# bitTree-Schem_2024-10-30.net
KiCad netlist of a schematic drawn in EasyEDA Pro
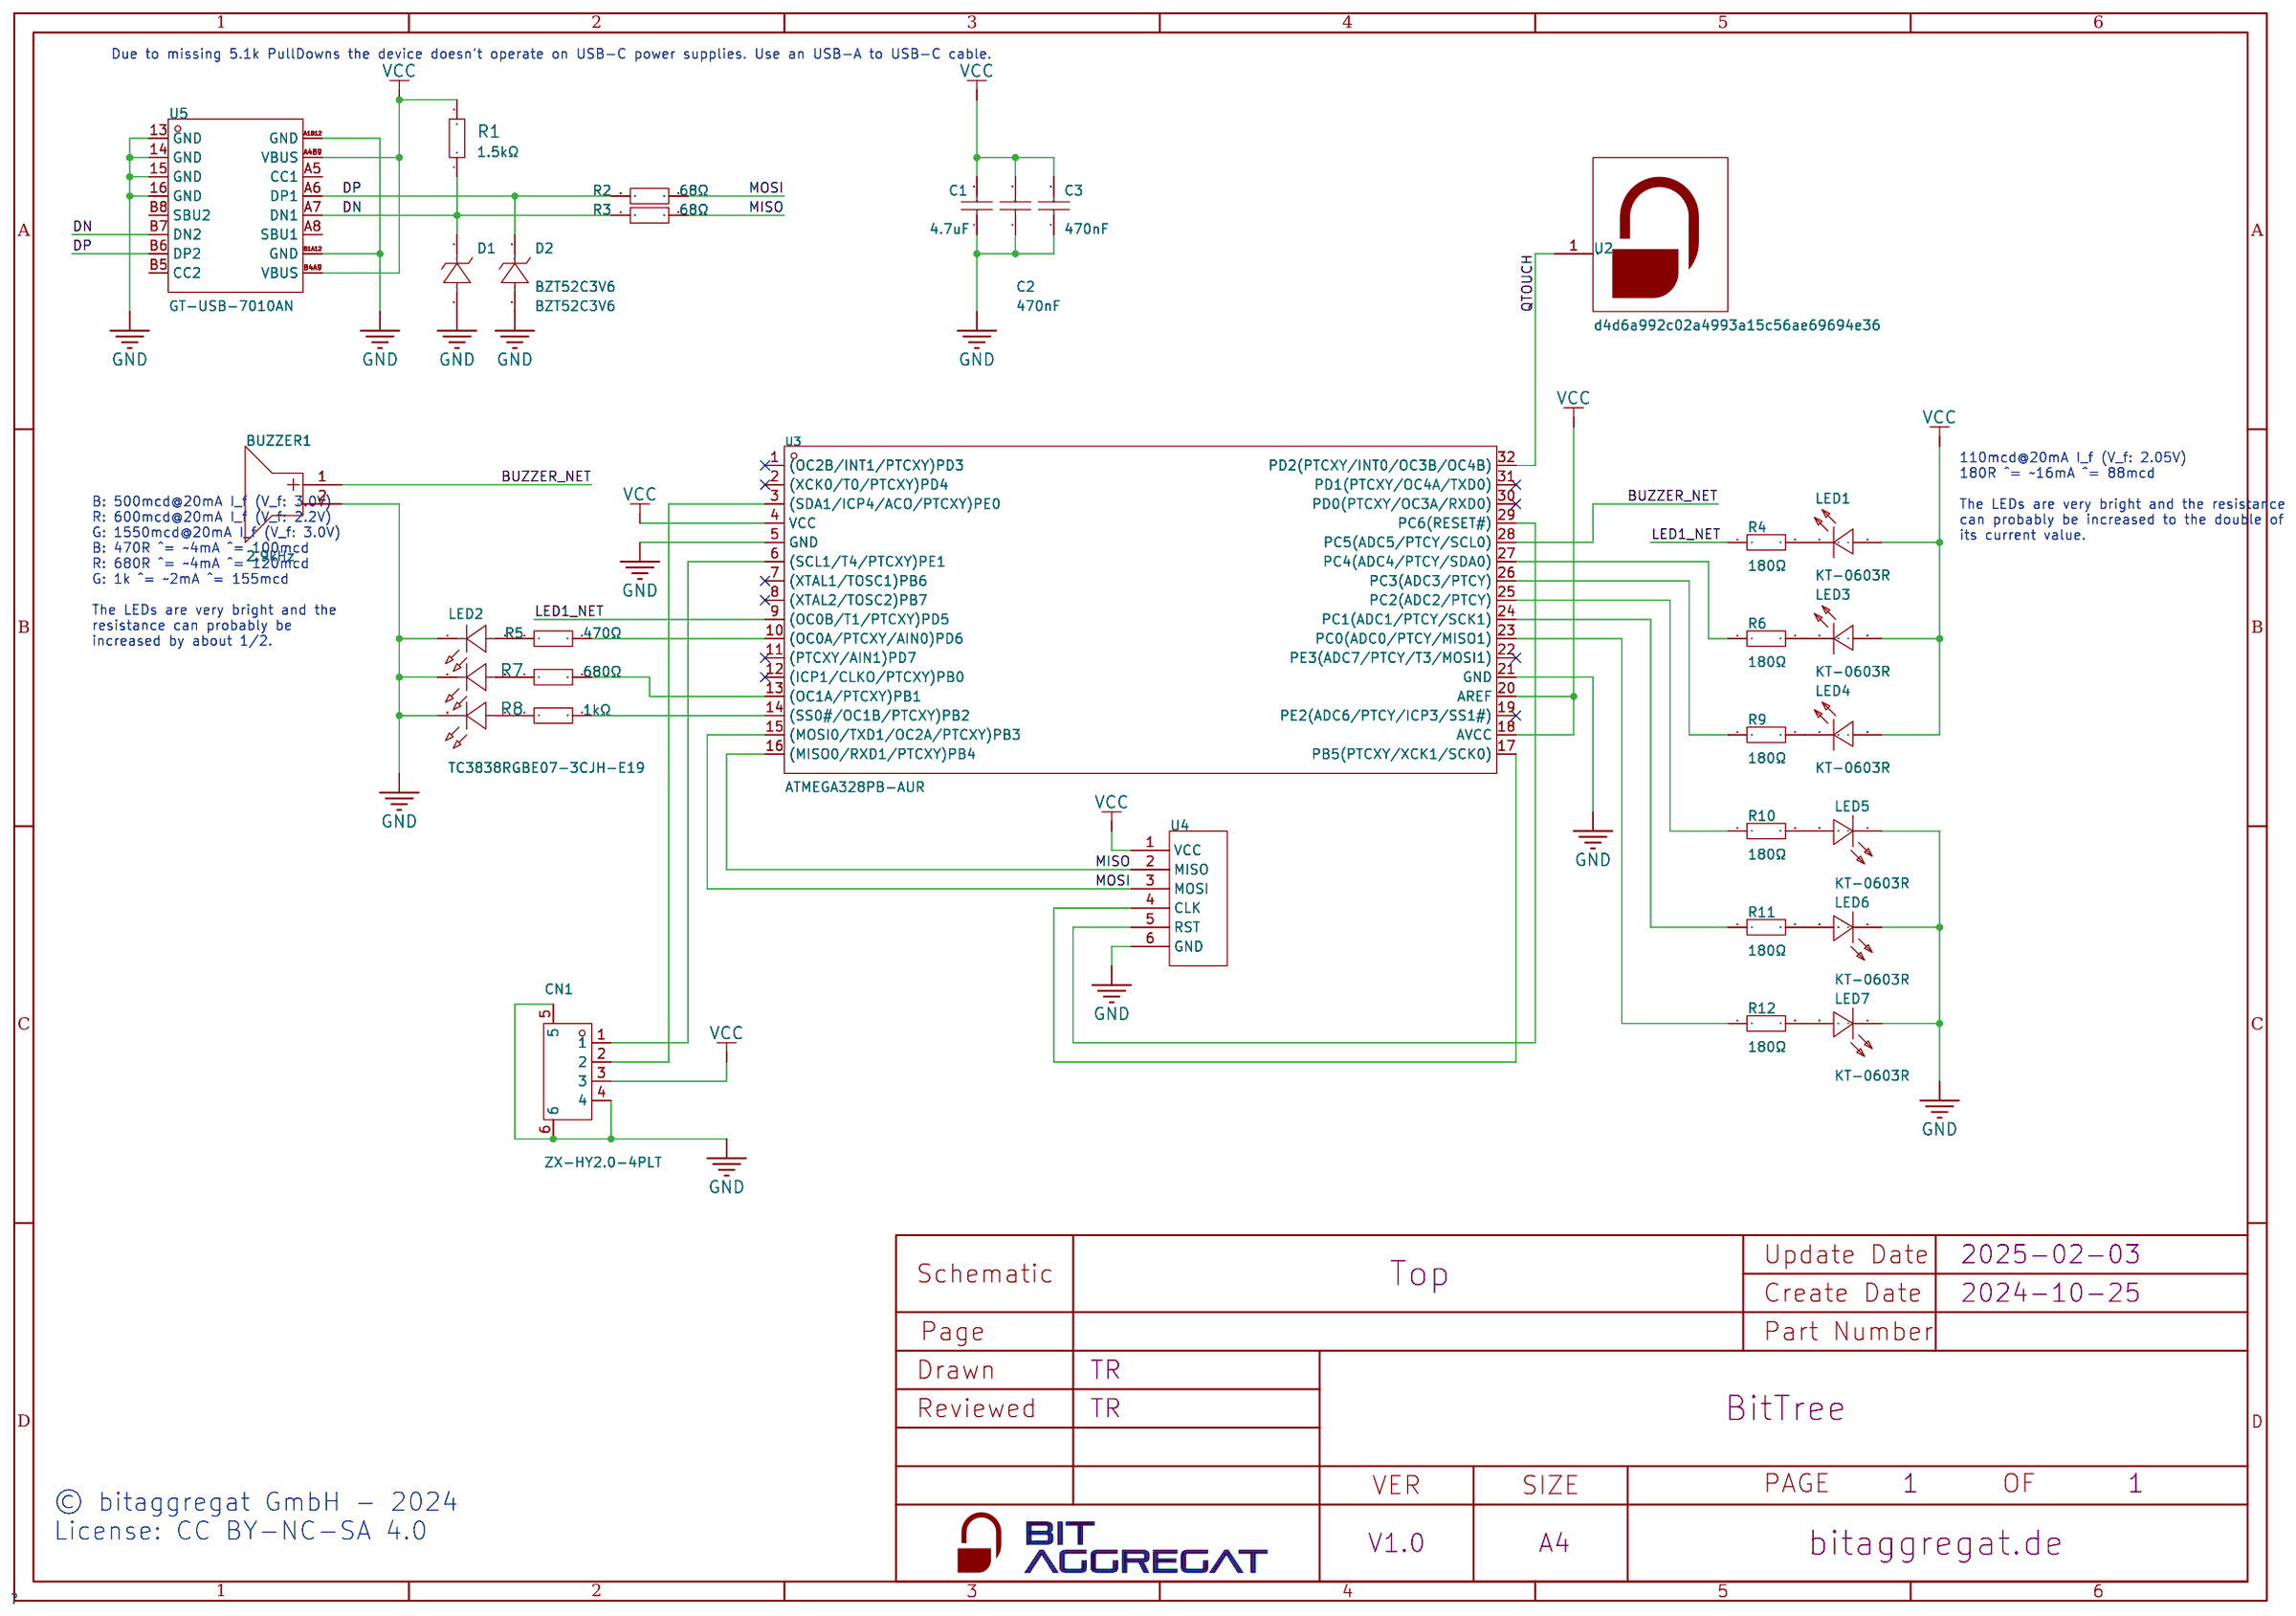
[diagram p0: schematic sheet]

(export (version "E")
  (design (tool "Eeschema 10.0.6"))
  (components
    (comp (ref "BUZZER1")
      (value "2.9kHz")
      (footprint "easyedapro:BUZ-TH_BD9.0-P5.00-D0.6-L-FD")
      (fields (field (name "Manufacturer Part") "Cy-9055-5029") (field (name "Manufacturer") "CY(超音)"))
      (libsource (lib "easyedapro") (part "CY-9055-5029"))
    )
    (comp (ref "C1")
      (value "4.7uF")
      (footprint "easyedapro:C0603")
      (fields
        (field (name "Manufacturer Part") "CL10A475KO8NNNC")
        (field (name "Manufacturer") "SAMSUNG(三星)")
      )
      (libsource (lib "easyedapro") (part "CL10A475KO8NNNC"))
    )
    (comp (ref "C2")
      (value "470nF")
      (footprint "easyedapro:C0603")
      (fields
        (field (name "Manufacturer Part") "CL10B474KA8NNNC")
        (field (name "Manufacturer") "SAMSUNG(三星)")
      )
      (libsource (lib "easyedapro") (part "CL10B474KA8NNNC"))
    )
    (comp (ref "C3")
      (value "470nF")
      (footprint "easyedapro:C0603")
      (fields
        (field (name "Manufacturer Part") "CL10B474KA8NNNC")
        (field (name "Manufacturer") "SAMSUNG(三星)")
      )
      (libsource (lib "easyedapro") (part "CL10B474KA8NNNC"))
    )
    (comp (ref "CN1")
      (value "ZX-HY2.0-4PLT")
      (footprint "easyedapro:CONN-SMD_4P-P2.00_HY2.0-4P")
      (fields (field (name "Manufacturer") "Megastar(兆星)"))
      (libsource (lib "easyedapro") (part "ZX-HY2.0-4PLT"))
    )
    (comp (ref "D1")
      (value "BZT52C3V6")
      (footprint "easyedapro:SOD-123_L2.7-W1.6-LS3.7-RD")
      (fields (field (name "Manufacturer") "宏迦橙"))
      (libsource (lib "easyedapro") (part "BZT52C3V6_C19077397"))
    )
    (comp (ref "D2")
      (value "BZT52C3V6")
      (footprint "easyedapro:SOD-123_L2.7-W1.6-LS3.7-RD")
      (fields (field (name "Manufacturer") "宏迦橙"))
      (libsource (lib "easyedapro") (part "BZT52C3V6_C19077397"))
    )
    (comp (ref "LED1")
      (value "KT-0603R")
      (footprint "easyedapro:LED0603-RD")
      (fields (field (name "Manufacturer") "KENTO"))
      (libsource (lib "easyedapro") (part "KT-0603R"))
    )
    (comp (ref "LED2")
      (value "TC3838RGBE07-3CJH-E19")
      (footprint "easyedapro:LED-SMD_6P-L3.5-W3.5-BL")
      (fields (field (name "Manufacturer") "TCWIN(天成)"))
      (libsource (lib "easyedapro") (part "TC3838RGBE07-3CJH-E19"))
    )
    (comp (ref "LED3")
      (value "KT-0603R")
      (footprint "easyedapro:LED0603-RD")
      (fields (field (name "Manufacturer") "KENTO"))
      (libsource (lib "easyedapro") (part "KT-0603R"))
    )
    (comp (ref "LED4")
      (value "KT-0603R")
      (footprint "easyedapro:LED0603-RD")
      (fields (field (name "Manufacturer") "KENTO"))
      (libsource (lib "easyedapro") (part "KT-0603R"))
    )
    (comp (ref "LED5")
      (value "KT-0603R")
      (footprint "easyedapro:LED0603-RD")
      (fields (field (name "Manufacturer") "KENTO"))
      (libsource (lib "easyedapro") (part "KT-0603R"))
    )
    (comp (ref "LED6")
      (value "KT-0603R")
      (footprint "easyedapro:LED0603-RD")
      (fields (field (name "Manufacturer") "KENTO"))
      (libsource (lib "easyedapro") (part "KT-0603R"))
    )
    (comp (ref "LED7")
      (value "KT-0603R")
      (footprint "easyedapro:LED0603-RD")
      (fields (field (name "Manufacturer") "KENTO"))
      (libsource (lib "easyedapro") (part "KT-0603R"))
    )
    (comp (ref "R1")
      (value "1.5kΩ")
      (footprint "easyedapro:R0603")
      (fields
        (field (name "Manufacturer Part") "0603WAF1501T5E")
        (field (name "Manufacturer") "UNI-ROYAL(厚声)")
      )
      (libsource (lib "easyedapro") (part "0603WAF1501T5E"))
    )
    (comp (ref "R2")
      (value "68Ω")
      (footprint "easyedapro:R0603")
      (fields
        (field (name "Manufacturer Part") "0603WAF680JT5E")
        (field (name "Manufacturer") "UNI-ROYAL(厚声)")
      )
      (libsource (lib "easyedapro") (part "0603WAF680JT5E"))
    )
    (comp (ref "R3")
      (value "68Ω")
      (footprint "easyedapro:R0603")
      (fields
        (field (name "Manufacturer Part") "0603WAF680JT5E")
        (field (name "Manufacturer") "UNI-ROYAL(厚声)")
      )
      (libsource (lib "easyedapro") (part "0603WAF680JT5E"))
    )
    (comp (ref "R4")
      (value "180Ω")
      (footprint "easyedapro:R0603")
      (fields
        (field (name "Manufacturer Part") "0603WAF1800T5E")
        (field (name "Manufacturer") "UNI-ROYAL(厚声)")
      )
      (libsource (lib "easyedapro") (part "0603WAF1800T5E"))
    )
    (comp (ref "R5")
      (value "470Ω")
      (footprint "easyedapro:R0603")
      (fields
        (field (name "Manufacturer Part") "0603WAF4700T5E")
        (field (name "Manufacturer") "UNI-ROYAL(厚声)")
      )
      (libsource (lib "easyedapro") (part "0603WAF4700T5E"))
    )
    (comp (ref "R6")
      (value "180Ω")
      (footprint "easyedapro:R0603")
      (fields
        (field (name "Manufacturer Part") "0603WAF1800T5E")
        (field (name "Manufacturer") "UNI-ROYAL(厚声)")
      )
      (libsource (lib "easyedapro") (part "0603WAF1800T5E"))
    )
    (comp (ref "R7")
      (value "680Ω")
      (footprint "easyedapro:R0603")
      (fields
        (field (name "Manufacturer Part") "0603WAF6800T5E")
        (field (name "Manufacturer") "UNI-ROYAL(厚声)")
      )
      (libsource (lib "easyedapro") (part "0603WAF6800T5E"))
    )
    (comp (ref "R8")
      (value "1kΩ")
      (footprint "easyedapro:R0603")
      (fields
        (field (name "Manufacturer Part") "0603WAF1001T5E")
        (field (name "Manufacturer") "UNI-ROYAL(厚声)")
      )
      (libsource (lib "easyedapro") (part "0603WAF1001T5E"))
    )
    (comp (ref "R9")
      (value "180Ω")
      (footprint "easyedapro:R0603")
      (fields
        (field (name "Manufacturer Part") "0603WAF1800T5E")
        (field (name "Manufacturer") "UNI-ROYAL(厚声)")
      )
      (libsource (lib "easyedapro") (part "0603WAF1800T5E"))
    )
    (comp (ref "R10")
      (value "180Ω")
      (footprint "easyedapro:R0603")
      (fields
        (field (name "Manufacturer Part") "0603WAF1800T5E")
        (field (name "Manufacturer") "UNI-ROYAL(厚声)")
      )
      (libsource (lib "easyedapro") (part "0603WAF1800T5E"))
    )
    (comp (ref "R11")
      (value "180Ω")
      (footprint "easyedapro:R0603")
      (fields
        (field (name "Manufacturer Part") "0603WAF1800T5E")
        (field (name "Manufacturer") "UNI-ROYAL(厚声)")
      )
      (libsource (lib "easyedapro") (part "0603WAF1800T5E"))
    )
    (comp (ref "R12")
      (value "180Ω")
      (footprint "easyedapro:R0603")
      (fields
        (field (name "Manufacturer Part") "0603WAF1800T5E")
        (field (name "Manufacturer") "UNI-ROYAL(厚声)")
      )
      (libsource (lib "easyedapro") (part "0603WAF1800T5E"))
    )
    (comp (ref "U2")
      (value "d4d6a992c02a4993a15c56ae69694e36")
      (footprint "easyedapro:QTouch-BA")
      (libsource (lib "easyedapro") (part "QTouch-BA"))
    )
    (comp (ref "U3")
      (value "ATMEGA328PB-AUR")
      (footprint "easyedapro:TQFP-32_L7.0-W7.0-P0.80-LS9.0-BL")
      (fields (field (name "Manufacturer") "MICROCHIP(美国微芯)"))
      (libsource (lib "easyedapro") (part "ATMEGA328PB-AUR"))
    )
    (comp (ref "U4")
      (value "~")
      (footprint "easyedapro:ProgrammingHeader")
      (libsource (lib "easyedapro") (part "ProgrammingHeader"))
    )
    (comp (ref "U5")
      (value "GT-USB-7010AN")
      (footprint "easyedapro:USB-SMD_GT-USB-7010AN")
      (fields (field (name "Manufacturer") "G-Switch(品赞)"))
      (libsource (lib "easyedapro") (part "GT-USB-7010AN"))
    )
  )
  (nets
    (net (code "1") (name "/BUZZER_NET") (class "Default")
      (node (ref "BUZZER1") (pin "1") (pinfunction "+_1") (pintype "input"))
      (node (ref "U3") (pin "28") (pinfunction "PC5(ADC5/PTCY/SCL0)_28") (pintype "input"))
    )
    (net (code "2") (name "/DN") (class "Default")
      (node (ref "D1") (pin "1") (pinfunction "K_1") (pintype "unspecified"))
      (node (ref "R1") (pin "1") (pinfunction "1_1") (pintype "input"))
      (node (ref "R3") (pin "1") (pinfunction "1_1") (pintype "input"))
      (node (ref "U5") (pin "A7") (pinfunction "DN1_A7") (pintype "unspecified"))
      (node (ref "U5") (pin "B7") (pinfunction "DN2_B7") (pintype "unspecified"))
    )
    (net (code "3") (name "/DP") (class "Default")
      (node (ref "D2") (pin "1") (pinfunction "K_1") (pintype "unspecified"))
      (node (ref "R2") (pin "1") (pinfunction "1_1") (pintype "input"))
      (node (ref "U5") (pin "A6") (pinfunction "DP1_A6") (pintype "unspecified"))
      (node (ref "U5") (pin "B6") (pinfunction "DP2_B6") (pintype "unspecified"))
    )
    (net (code "4") (name "/LED1_NET") (class "Default")
      (node (ref "R4") (pin "1") (pinfunction "1_1") (pintype "input"))
      (node (ref "U3") (pin "9") (pinfunction "(OC0B/T1/PTCXY)PD5_9") (pintype "input"))
    )
    (net (code "5") (name "/MISO") (class "Default")
      (node (ref "R3") (pin "2") (pinfunction "2_2") (pintype "input"))
      (node (ref "U3") (pin "16") (pinfunction "(MISO0/RXD1/PTCXY)PB4_16") (pintype "input"))
      (node (ref "U4") (pin "2") (pinfunction "MISO_2") (pintype "input"))
    )
    (net (code "6") (name "/MOSI") (class "Default")
      (node (ref "R2") (pin "2") (pinfunction "2_2") (pintype "input"))
      (node (ref "U3") (pin "15") (pinfunction "(MOSI0/TXD1/OC2A/PTCXY)PB3_15") (pintype "input"))
      (node (ref "U4") (pin "3") (pinfunction "MOSI_3") (pintype "input"))
    )
    (net (code "7") (name "/QTOUCH") (class "Default")
      (node (ref "U2") (pin "1") (pinfunction "1_1") (pintype "input"))
      (node (ref "U3") (pin "32") (pinfunction "PD2(PTCXY/INT0/OC3B/OC4B)_32") (pintype "input"))
    )
    (net (code "8") (name "GND") (class "Default")
      (node (ref "BUZZER1") (pin "2") (pinfunction "-_2") (pintype "input"))
      (node (ref "C1") (pin "1") (pinfunction "1_1") (pintype "input"))
      (node (ref "C2") (pin "1") (pinfunction "1_1") (pintype "input"))
      (node (ref "C3") (pin "1") (pinfunction "1_1") (pintype "input"))
      (node (ref "CN1") (pin "4") (pinfunction "4_4") (pintype "unspecified"))
      (node (ref "CN1") (pin "5") (pinfunction "5_5") (pintype "unspecified"))
      (node (ref "CN1") (pin "6") (pinfunction "6_6") (pintype "unspecified"))
      (node (ref "D1") (pin "2") (pinfunction "A_2") (pintype "unspecified"))
      (node (ref "D2") (pin "2") (pinfunction "A_2") (pintype "unspecified"))
      (node (ref "LED2") (pin "4") (pinfunction "-_4") (pintype "unspecified"))
      (node (ref "LED2") (pin "5") (pinfunction "-_5") (pintype "unspecified"))
      (node (ref "LED2") (pin "6") (pinfunction "-_6") (pintype "unspecified"))
      (node (ref "LED5") (pin "1") (pinfunction "K_1") (pintype "unspecified"))
      (node (ref "LED6") (pin "1") (pinfunction "K_1") (pintype "unspecified"))
      (node (ref "LED7") (pin "1") (pinfunction "K_1") (pintype "unspecified"))
      (node (ref "U3") (pin "21") (pinfunction "GND_21") (pintype "input"))
      (node (ref "U3") (pin "5") (pinfunction "GND_5") (pintype "input"))
      (node (ref "U4") (pin "6") (pinfunction "GND_6") (pintype "input"))
      (node (ref "U5") (pin "13") (pinfunction "GND_13") (pintype "unspecified"))
      (node (ref "U5") (pin "14") (pinfunction "GND_14") (pintype "unspecified"))
      (node (ref "U5") (pin "15") (pinfunction "GND_15") (pintype "unspecified"))
      (node (ref "U5") (pin "16") (pinfunction "GND_16") (pintype "unspecified"))
      (node (ref "U5") (pin "A1B12") (pinfunction "GND_A1B12") (pintype "unspecified"))
      (node (ref "U5") (pin "B1A12") (pinfunction "GND_B1A12") (pintype "unspecified"))
    )
    (net (code "9") (name "Net-(LED1-K)") (class "Default")
      (node (ref "LED1") (pin "1") (pinfunction "K_1") (pintype "unspecified"))
      (node (ref "R4") (pin "2") (pinfunction "2_2") (pintype "input"))
    )
    (net (code "10") (name "Net-(LED2-+-Pad1)") (class "Default")
      (node (ref "LED2") (pin "1") (pinfunction "+_1") (pintype "unspecified"))
      (node (ref "R8") (pin "1") (pinfunction "1_1") (pintype "input"))
    )
    (net (code "11") (name "Net-(LED2-+-Pad2)") (class "Default")
      (node (ref "LED2") (pin "2") (pinfunction "+_2") (pintype "unspecified"))
      (node (ref "R7") (pin "1") (pinfunction "1_1") (pintype "input"))
    )
    (net (code "12") (name "Net-(LED2-+-Pad3)") (class "Default")
      (node (ref "LED2") (pin "3") (pinfunction "+_3") (pintype "unspecified"))
      (node (ref "R5") (pin "1") (pinfunction "1_1") (pintype "input"))
    )
    (net (code "13") (name "Net-(LED3-K)") (class "Default")
      (node (ref "LED3") (pin "1") (pinfunction "K_1") (pintype "unspecified"))
      (node (ref "R6") (pin "2") (pinfunction "2_2") (pintype "input"))
    )
    (net (code "14") (name "Net-(LED4-K)") (class "Default")
      (node (ref "LED4") (pin "1") (pinfunction "K_1") (pintype "unspecified"))
      (node (ref "R9") (pin "2") (pinfunction "2_2") (pintype "input"))
    )
    (net (code "15") (name "Net-(LED5-A)") (class "Default")
      (node (ref "LED5") (pin "2") (pinfunction "A_2") (pintype "unspecified"))
      (node (ref "R10") (pin "2") (pinfunction "2_2") (pintype "input"))
    )
    (net (code "16") (name "Net-(LED6-A)") (class "Default")
      (node (ref "LED6") (pin "2") (pinfunction "A_2") (pintype "unspecified"))
      (node (ref "R11") (pin "2") (pinfunction "2_2") (pintype "input"))
    )
    (net (code "17") (name "Net-(LED7-A)") (class "Default")
      (node (ref "LED7") (pin "2") (pinfunction "A_2") (pintype "unspecified"))
      (node (ref "R12") (pin "2") (pinfunction "2_2") (pintype "input"))
    )
    (net (code "18") (name "Net-(U3-(OC0A{slash}PTCXY{slash}AIN0)PD6)") (class "Default")
      (node (ref "R5") (pin "2") (pinfunction "2_2") (pintype "input"))
      (node (ref "U3") (pin "10") (pinfunction "(OC0A/PTCXY/AIN0)PD6_10") (pintype "input"))
    )
    (net (code "19") (name "Net-(U3-(OC1A{slash}PTCXY)PB1)") (class "Default")
      (node (ref "R7") (pin "2") (pinfunction "2_2") (pintype "input"))
      (node (ref "U3") (pin "13") (pinfunction "(OC1A/PTCXY)PB1_13") (pintype "input"))
    )
    (net (code "20") (name "Net-(U3-(SCL1{slash}T4{slash}PTCXY)PE1)") (class "Default")
      (node (ref "CN1") (pin "1") (pinfunction "1_1") (pintype "unspecified"))
      (node (ref "U3") (pin "6") (pinfunction "(SCL1/T4/PTCXY)PE1_6") (pintype "input"))
    )
    (net (code "21") (name "Net-(U3-(SDA1{slash}ICP4{slash}ACO{slash}PTCXY)PE0)") (class "Default")
      (node (ref "CN1") (pin "2") (pinfunction "2_2") (pintype "unspecified"))
      (node (ref "U3") (pin "3") (pinfunction "(SDA1/ICP4/ACO/PTCXY)PE0_3") (pintype "input"))
    )
    (net (code "22") (name "Net-(U3-(SS0#{slash}OC1B{slash}PTCXY)PB2)") (class "Default")
      (node (ref "R8") (pin "2") (pinfunction "2_2") (pintype "input"))
      (node (ref "U3") (pin "14") (pinfunction "(SS0#/OC1B/PTCXY)PB2_14") (pintype "input"))
    )
    (net (code "23") (name "Net-(U3-PB5(PTCXY{slash}XCK1{slash}SCK0))") (class "Default")
      (node (ref "U3") (pin "17") (pinfunction "PB5(PTCXY/XCK1/SCK0)_17") (pintype "input"))
      (node (ref "U4") (pin "4") (pinfunction "CLK_4") (pintype "input"))
    )
    (net (code "24") (name "Net-(U3-PC0(ADC0{slash}PTCY{slash}MISO1))") (class "Default")
      (node (ref "R12") (pin "1") (pinfunction "1_1") (pintype "input"))
      (node (ref "U3") (pin "23") (pinfunction "PC0(ADC0/PTCY/MISO1)_23") (pintype "input"))
    )
    (net (code "25") (name "Net-(U3-PC1(ADC1{slash}PTCY{slash}SCK1))") (class "Default")
      (node (ref "R11") (pin "1") (pinfunction "1_1") (pintype "input"))
      (node (ref "U3") (pin "24") (pinfunction "PC1(ADC1/PTCY/SCK1)_24") (pintype "input"))
    )
    (net (code "26") (name "Net-(U3-PC2(ADC2{slash}PTCY))") (class "Default")
      (node (ref "R10") (pin "1") (pinfunction "1_1") (pintype "input"))
      (node (ref "U3") (pin "25") (pinfunction "PC2(ADC2/PTCY)_25") (pintype "input"))
    )
    (net (code "27") (name "Net-(U3-PC3(ADC3{slash}PTCY))") (class "Default")
      (node (ref "R9") (pin "1") (pinfunction "1_1") (pintype "input"))
      (node (ref "U3") (pin "26") (pinfunction "PC3(ADC3/PTCY)_26") (pintype "input"))
    )
    (net (code "28") (name "Net-(U3-PC4(ADC4{slash}PTCY{slash}SDA0))") (class "Default")
      (node (ref "R6") (pin "1") (pinfunction "1_1") (pintype "input"))
      (node (ref "U3") (pin "27") (pinfunction "PC4(ADC4/PTCY/SDA0)_27") (pintype "input"))
    )
    (net (code "29") (name "Net-(U3-PC6(RESET#))") (class "Default")
      (node (ref "U3") (pin "29") (pinfunction "PC6(RESET#)_29") (pintype "input"))
      (node (ref "U4") (pin "5") (pinfunction "RST_5") (pintype "input"))
    )
    (net (code "30") (name "VCC") (class "Default")
      (node (ref "C1") (pin "2") (pinfunction "2_2") (pintype "input"))
      (node (ref "C2") (pin "2") (pinfunction "2_2") (pintype "input"))
      (node (ref "C3") (pin "2") (pinfunction "2_2") (pintype "input"))
      (node (ref "CN1") (pin "3") (pinfunction "3_3") (pintype "unspecified"))
      (node (ref "LED1") (pin "2") (pinfunction "A_2") (pintype "unspecified"))
      (node (ref "LED3") (pin "2") (pinfunction "A_2") (pintype "unspecified"))
      (node (ref "LED4") (pin "2") (pinfunction "A_2") (pintype "unspecified"))
      (node (ref "R1") (pin "2") (pinfunction "2_2") (pintype "input"))
      (node (ref "U3") (pin "18") (pinfunction "AVCC_18") (pintype "input"))
      (node (ref "U3") (pin "20") (pinfunction "AREF_20") (pintype "input"))
      (node (ref "U3") (pin "4") (pinfunction "VCC_4") (pintype "input"))
      (node (ref "U4") (pin "1") (pinfunction "VCC_1") (pintype "input"))
      (node (ref "U5") (pin "A4B9") (pinfunction "VBUS_A4B9") (pintype "unspecified"))
      (node (ref "U5") (pin "B4A9") (pinfunction "VBUS_B4A9") (pintype "unspecified"))
    )
    (net (code "31") (name "unconnected-(U3-(ICP1{slash}CLKO{slash}PTCXY)PB0-Pad12)") (class "Default")
      (node (ref "U3") (pin "12") (pinfunction "(ICP1/CLKO/PTCXY)PB0_12") (pintype "input+no_connect"))
    )
    (net (code "32") (name "unconnected-(U3-(OC2B{slash}INT1{slash}PTCXY)PD3-Pad1)") (class "Default")
      (node (ref "U3") (pin "1") (pinfunction "(OC2B/INT1/PTCXY)PD3_1") (pintype "input+no_connect"))
    )
    (net (code "33") (name "unconnected-(U3-(PTCXY{slash}AIN1)PD7-Pad11)") (class "Default")
      (node (ref "U3") (pin "11") (pinfunction "(PTCXY/AIN1)PD7_11") (pintype "input+no_connect"))
    )
    (net (code "34") (name "unconnected-(U3-(XCK0{slash}T0{slash}PTCXY)PD4-Pad2)") (class "Default")
      (node (ref "U3") (pin "2") (pinfunction "(XCK0/T0/PTCXY)PD4_2") (pintype "input+no_connect"))
    )
    (net (code "35") (name "unconnected-(U3-(XTAL1{slash}TOSC1)PB6-Pad7)") (class "Default")
      (node (ref "U3") (pin "7") (pinfunction "(XTAL1/TOSC1)PB6_7") (pintype "input+no_connect"))
    )
    (net (code "36") (name "unconnected-(U3-(XTAL2{slash}TOSC2)PB7-Pad8)") (class "Default")
      (node (ref "U3") (pin "8") (pinfunction "(XTAL2/TOSC2)PB7_8") (pintype "input+no_connect"))
    )
    (net (code "37") (name "unconnected-(U3-PD0(PTCXY{slash}OC3A{slash}RXD0)-Pad30)") (class "Default")
      (node (ref "U3") (pin "30") (pinfunction "PD0(PTCXY/OC3A/RXD0)_30") (pintype "input+no_connect"))
    )
    (net (code "38") (name "unconnected-(U3-PD1(PTCXY{slash}OC4A{slash}TXD0)-Pad31)") (class "Default")
      (node (ref "U3") (pin "31") (pinfunction "PD1(PTCXY/OC4A/TXD0)_31") (pintype "input+no_connect"))
    )
    (net (code "39") (name "unconnected-(U3-PE2(ADC6{slash}PTCY{slash}ICP3{slash}SS1#)-Pad19)") (class "Default")
      (node (ref "U3") (pin "19") (pinfunction "PE2(ADC6/PTCY/ICP3/SS1#)_19") (pintype "input+no_connect"))
    )
    (net (code "40") (name "unconnected-(U3-PE3(ADC7{slash}PTCY{slash}T3{slash}MOSI1)-Pad22)") (class "Default")
      (node (ref "U3") (pin "22") (pinfunction "PE3(ADC7/PTCY/T3/MOSI1)_22") (pintype "input+no_connect"))
    )
    (net (code "41") (name "unconnected-(U5-CC1-PadA5)") (class "Default")
      (node (ref "U5") (pin "A5") (pinfunction "CC1_A5") (pintype "unspecified"))
    )
    (net (code "42") (name "unconnected-(U5-CC2-PadB5)") (class "Default")
      (node (ref "U5") (pin "B5") (pinfunction "CC2_B5") (pintype "unspecified"))
    )
    (net (code "43") (name "unconnected-(U5-SBU1-PadA8)") (class "Default")
      (node (ref "U5") (pin "A8") (pinfunction "SBU1_A8") (pintype "unspecified"))
    )
    (net (code "44") (name "unconnected-(U5-SBU2-PadB8)") (class "Default")
      (node (ref "U5") (pin "B8") (pinfunction "SBU2_B8") (pintype "unspecified"))
    )
  )
)
